# amp-LNA-TQP3M9036.net
KiCad netlist of a schematic drawn in EAGLE
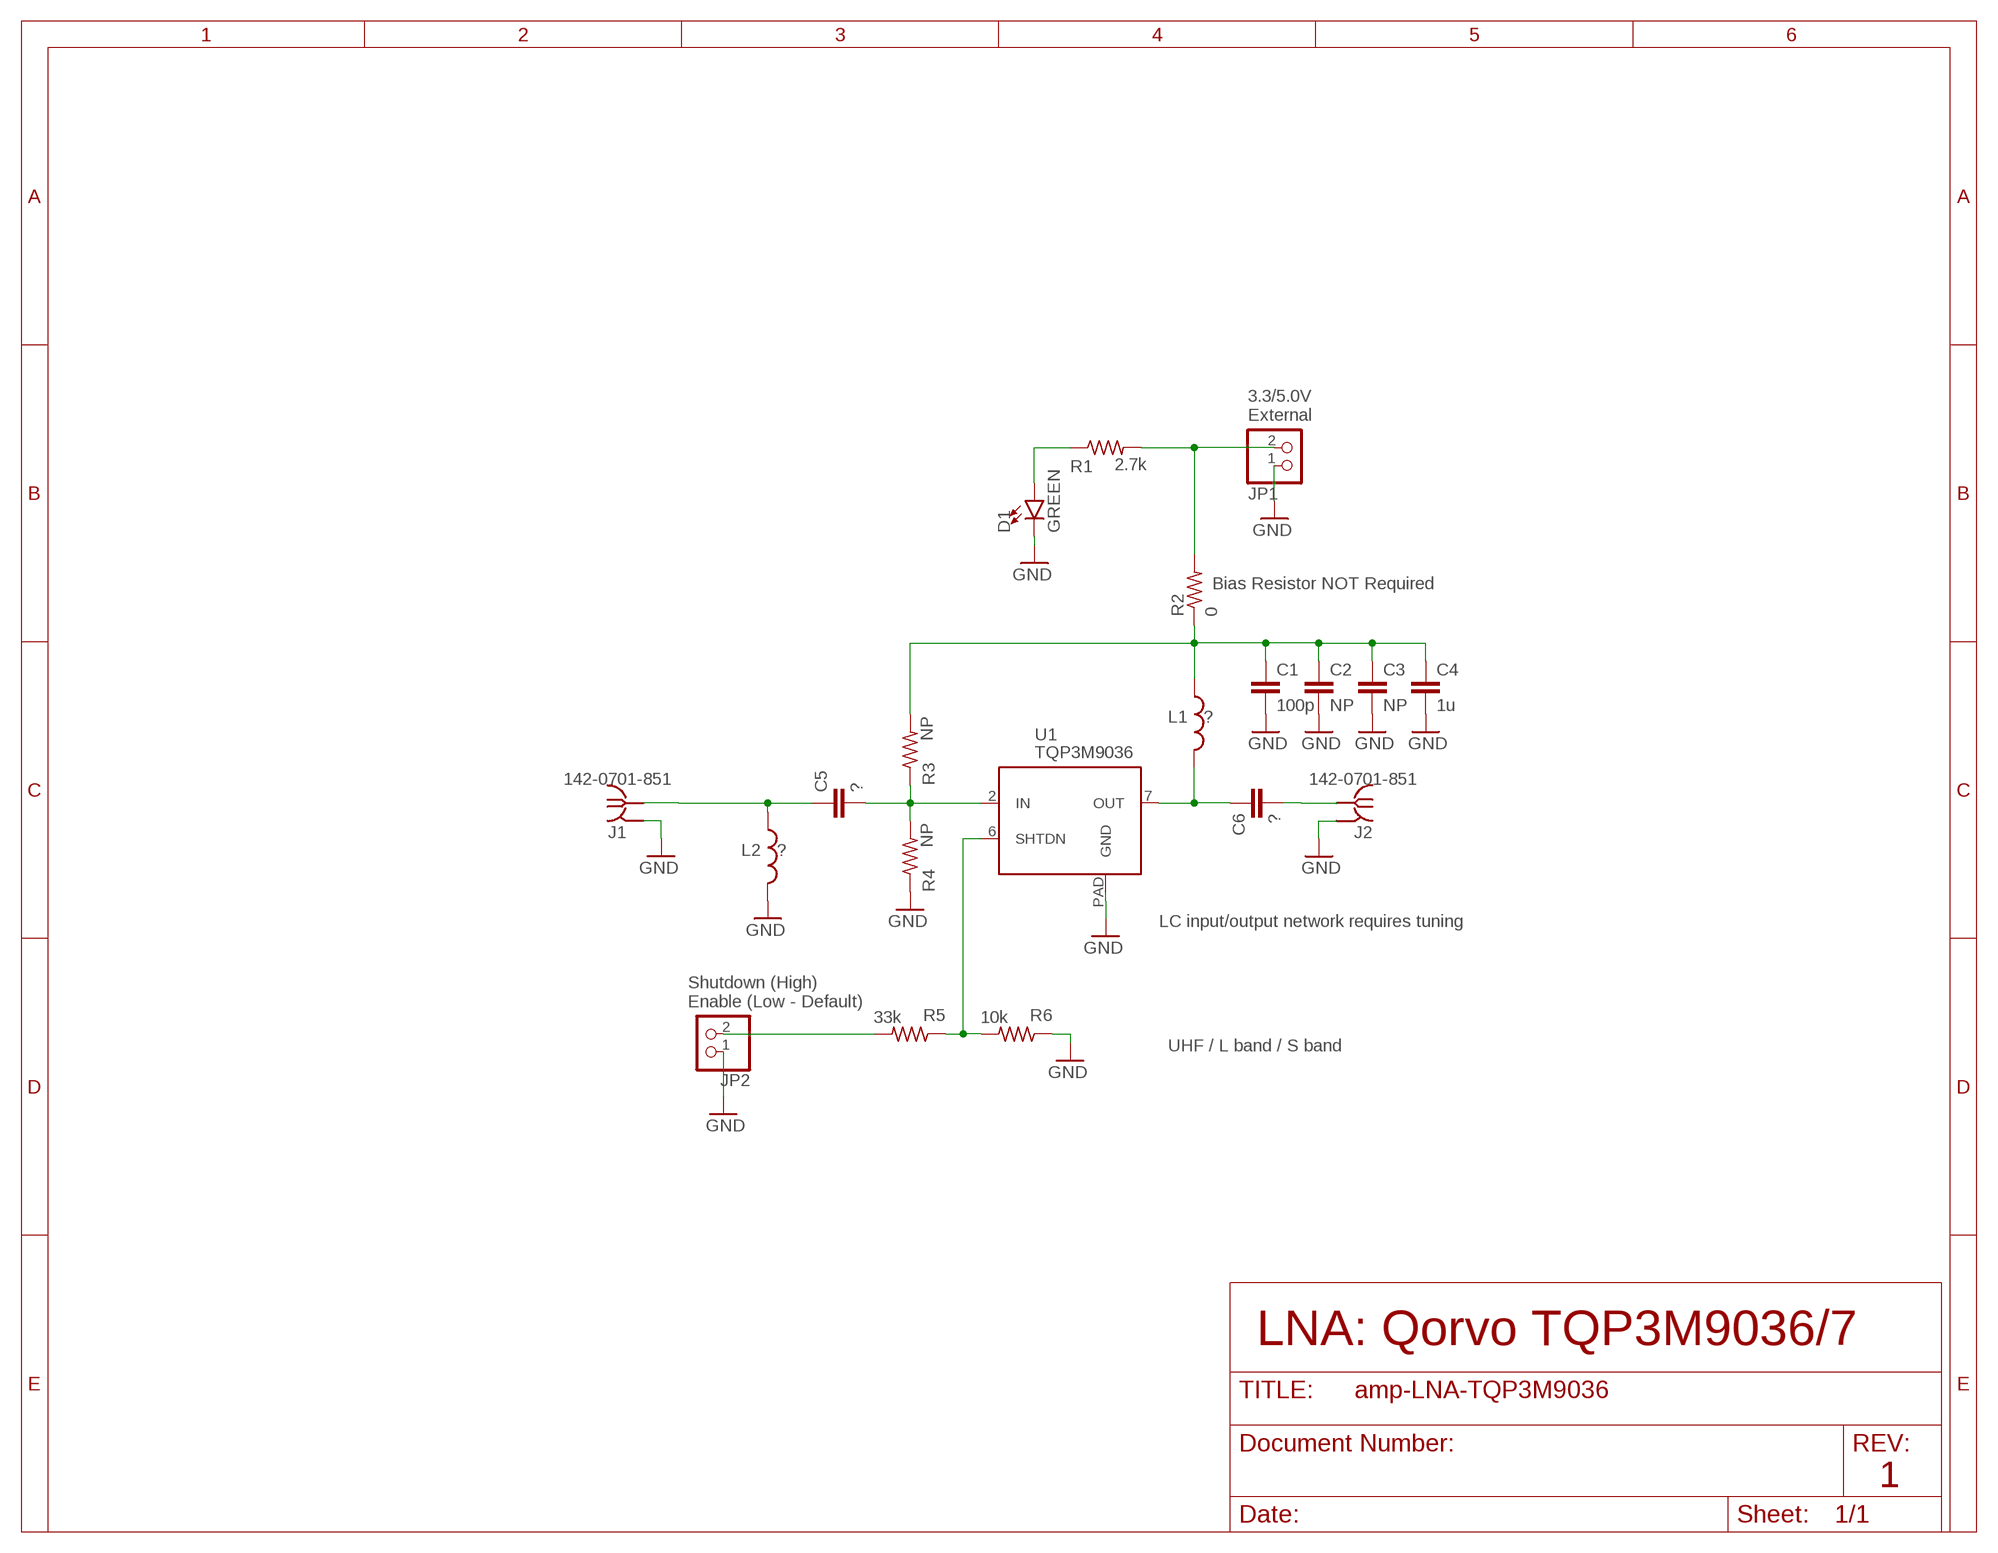
[diagram p0: schematic, sheet 1]

(export (version "E")
  (design (tool "Eeschema 10.0.6"))
  (components
    (comp (ref "C1")
      (value "100p")
      (footprint "eagle-import:.0603-B-NOSILK")
      (libsource (lib "eagle-import") (part "C-EU0603-B-NOSILK"))
    )
    (comp (ref "C2")
      (value "NP")
      (footprint "eagle-import:.0603-B-NOSILK")
      (libsource (lib "eagle-import") (part "C-EU0603-B-NOSILK"))
    )
    (comp (ref "C3")
      (value "NP")
      (footprint "eagle-import:.0603-B-NOSILK")
      (libsource (lib "eagle-import") (part "C-EU0603-B-NOSILK"))
    )
    (comp (ref "C4")
      (value "1u")
      (footprint "eagle-import:.0603-B-NOSILK")
      (libsource (lib "eagle-import") (part "C-EU0603-B-NOSILK"))
    )
    (comp (ref "C5")
      (value "?")
      (footprint "eagle-import:.0402-B-NOSILK")
      (libsource (lib "eagle-import") (part "C-EU0402-B-NOSILK"))
    )
    (comp (ref "C6")
      (value "?")
      (footprint "eagle-import:.0402-B-NOSILK")
      (libsource (lib "eagle-import") (part "C-EU0402-B-NOSILK"))
    )
    (comp (ref "D1")
      (value "GREEN")
      (footprint "eagle-import:LED-0603")
      (libsource (lib "eagle-import") (part "LED-GREEN0603"))
    )
    (comp (ref "J1")
      (value "142-0701-851")
      (footprint "eagle-import:142-0701-851")
      (libsource (lib "eagle-import") (part "142-0701-851"))
    )
    (comp (ref "J2")
      (value "142-0701-851")
      (footprint "eagle-import:142-0701-851")
      (libsource (lib "eagle-import") (part "142-0701-851"))
    )
    (comp (ref "JP1")
      (value "PINHD-1X2")
      (footprint "eagle-import:1X02")
      (libsource (lib "eagle-import") (part "PINHD-1X2"))
    )
    (comp (ref "JP2")
      (value "PINHD-1X2")
      (footprint "eagle-import:1X02")
      (libsource (lib "eagle-import") (part "PINHD-1X2"))
    )
    (comp (ref "L1")
      (value "?")
      (footprint "eagle-import:.0603-B-NOSILK")
      (libsource (lib "eagle-import") (part "L-US0603-B-NOSILK"))
    )
    (comp (ref "L2")
      (value "?")
      (footprint "eagle-import:.0402-B-NOSILK")
      (libsource (lib "eagle-import") (part "L-US0402-B-NOSILK"))
    )
    (comp (ref "R1")
      (value "2.7k")
      (footprint "eagle-import:.0603-B-NOSILK")
      (libsource (lib "eagle-import") (part "R-US_0603-B-NOSILK"))
    )
    (comp (ref "R2")
      (value "0")
      (footprint "eagle-import:.0805-B-NOSILK")
      (libsource (lib "eagle-import") (part "R-US_0805-B-NOSILK"))
    )
    (comp (ref "R3")
      (value "NP")
      (footprint "eagle-import:.0402-B-NOSILK")
      (libsource (lib "eagle-import") (part "R-US_0402-B-NOSILK"))
    )
    (comp (ref "R4")
      (value "NP")
      (footprint "eagle-import:.0402-B-NOSILK")
      (libsource (lib "eagle-import") (part "R-US_0402-B-NOSILK"))
    )
    (comp (ref "R5")
      (value "33k")
      (footprint "eagle-import:.0603-B-NOSILK")
      (libsource (lib "eagle-import") (part "R-US_0603-B-NOSILK"))
    )
    (comp (ref "R6")
      (value "10k")
      (footprint "eagle-import:.0603-B-NOSILK")
      (libsource (lib "eagle-import") (part "R-US_0603-B-NOSILK"))
    )
    (comp (ref "U1")
      (value "TQP3M9036")
      (footprint "eagle-import:DFN8-2X2-WITH-PAD")
      (libsource (lib "eagle-import") (part "TQP3M9036"))
    )
  )
  (nets
    (net (code "1") (name "GND") (class "Default")
      (node (ref "C1") (pin "2") (pinfunction "2_2") (pintype "passive"))
      (node (ref "C2") (pin "2") (pinfunction "2_2") (pintype "passive"))
      (node (ref "C3") (pin "2") (pinfunction "2_2") (pintype "passive"))
      (node (ref "C4") (pin "2") (pinfunction "2_2") (pintype "passive"))
      (node (ref "D1") (pin "C") (pinfunction "C_C") (pintype "passive"))
      (node (ref "J1") (pin "GND1") (pinfunction "GND_GND1") (pintype "bidirectional"))
      (node (ref "J1") (pin "GND2") (pinfunction "GND_GND2") (pintype "bidirectional"))
      (node (ref "J1") (pin "GND3") (pinfunction "GND_GND3") (pintype "bidirectional"))
      (node (ref "J1") (pin "GND4") (pinfunction "GND_GND4") (pintype "bidirectional"))
      (node (ref "J2") (pin "GND1") (pinfunction "GND_GND1") (pintype "bidirectional"))
      (node (ref "J2") (pin "GND2") (pinfunction "GND_GND2") (pintype "bidirectional"))
      (node (ref "J2") (pin "GND3") (pinfunction "GND_GND3") (pintype "bidirectional"))
      (node (ref "J2") (pin "GND4") (pinfunction "GND_GND4") (pintype "bidirectional"))
      (node (ref "JP1") (pin "1") (pinfunction "1_1") (pintype "passive"))
      (node (ref "JP2") (pin "1") (pinfunction "1_1") (pintype "passive"))
      (node (ref "L2") (pin "2") (pinfunction "2_2") (pintype "passive"))
      (node (ref "R4") (pin "1") (pinfunction "1_1") (pintype "passive"))
      (node (ref "R6") (pin "1") (pinfunction "1_1") (pintype "passive"))
      (node (ref "U1") (pin "PAD") (pinfunction "GND_PAD") (pintype "power_in"))
    )
    (net (code "2") (name "Net-(C1-Pad1)") (class "Default")
      (node (ref "C1") (pin "1") (pinfunction "1_1") (pintype "passive"))
      (node (ref "C2") (pin "1") (pinfunction "1_1") (pintype "passive"))
      (node (ref "C3") (pin "1") (pinfunction "1_1") (pintype "passive"))
      (node (ref "C4") (pin "1") (pinfunction "1_1") (pintype "passive"))
      (node (ref "L1") (pin "1") (pinfunction "1_1") (pintype "passive"))
      (node (ref "R2") (pin "1") (pinfunction "1_1") (pintype "passive"))
      (node (ref "R3") (pin "2") (pinfunction "2_2") (pintype "passive"))
    )
    (net (code "3") (name "Net-(D1-PadA)") (class "Default")
      (node (ref "D1") (pin "A") (pinfunction "A_A") (pintype "passive"))
      (node (ref "R1") (pin "1") (pinfunction "1_1") (pintype "passive"))
    )
    (net (code "4") (name "Net-(J1-RF)") (class "Default")
      (node (ref "C5") (pin "1") (pinfunction "1_1") (pintype "passive"))
      (node (ref "J1") (pin "RF1") (pinfunction "RF_RF1") (pintype "bidirectional"))
      (node (ref "L2") (pin "1") (pinfunction "1_1") (pintype "passive"))
    )
    (net (code "5") (name "Net-(J2-RF)") (class "Default")
      (node (ref "C6") (pin "2") (pinfunction "2_2") (pintype "passive"))
      (node (ref "J2") (pin "RF1") (pinfunction "RF_RF1") (pintype "bidirectional"))
    )
    (net (code "6") (name "Net-(JP1-Pad2)") (class "Default")
      (node (ref "JP1") (pin "2") (pinfunction "2_2") (pintype "passive"))
      (node (ref "R1") (pin "2") (pinfunction "2_2") (pintype "passive"))
      (node (ref "R2") (pin "2") (pinfunction "2_2") (pintype "passive"))
    )
    (net (code "7") (name "Net-(JP2-Pad2)") (class "Default")
      (node (ref "JP2") (pin "2") (pinfunction "2_2") (pintype "passive"))
      (node (ref "R5") (pin "2") (pinfunction "2_2") (pintype "passive"))
    )
    (net (code "8") (name "Net-(U1-IN)") (class "Default")
      (node (ref "C5") (pin "2") (pinfunction "2_2") (pintype "passive"))
      (node (ref "R3") (pin "1") (pinfunction "1_1") (pintype "passive"))
      (node (ref "R4") (pin "2") (pinfunction "2_2") (pintype "passive"))
      (node (ref "U1") (pin "2") (pinfunction "IN_2") (pintype "input"))
    )
    (net (code "9") (name "Net-(U1-OUT)") (class "Default")
      (node (ref "C6") (pin "1") (pinfunction "1_1") (pintype "passive"))
      (node (ref "L1") (pin "2") (pinfunction "2_2") (pintype "passive"))
      (node (ref "U1") (pin "7") (pinfunction "OUT_7") (pintype "output"))
    )
    (net (code "10") (name "Net-(U1-SHTDN)") (class "Default")
      (node (ref "R5") (pin "1") (pinfunction "1_1") (pintype "passive"))
      (node (ref "R6") (pin "2") (pinfunction "2_2") (pintype "passive"))
      (node (ref "U1") (pin "6") (pinfunction "SHTDN_6") (pintype "input"))
    )
  )
)
